# NANO_Mystical_Ouija_Board.net
KiCad netlist of a schematic drawn in EasyEDA
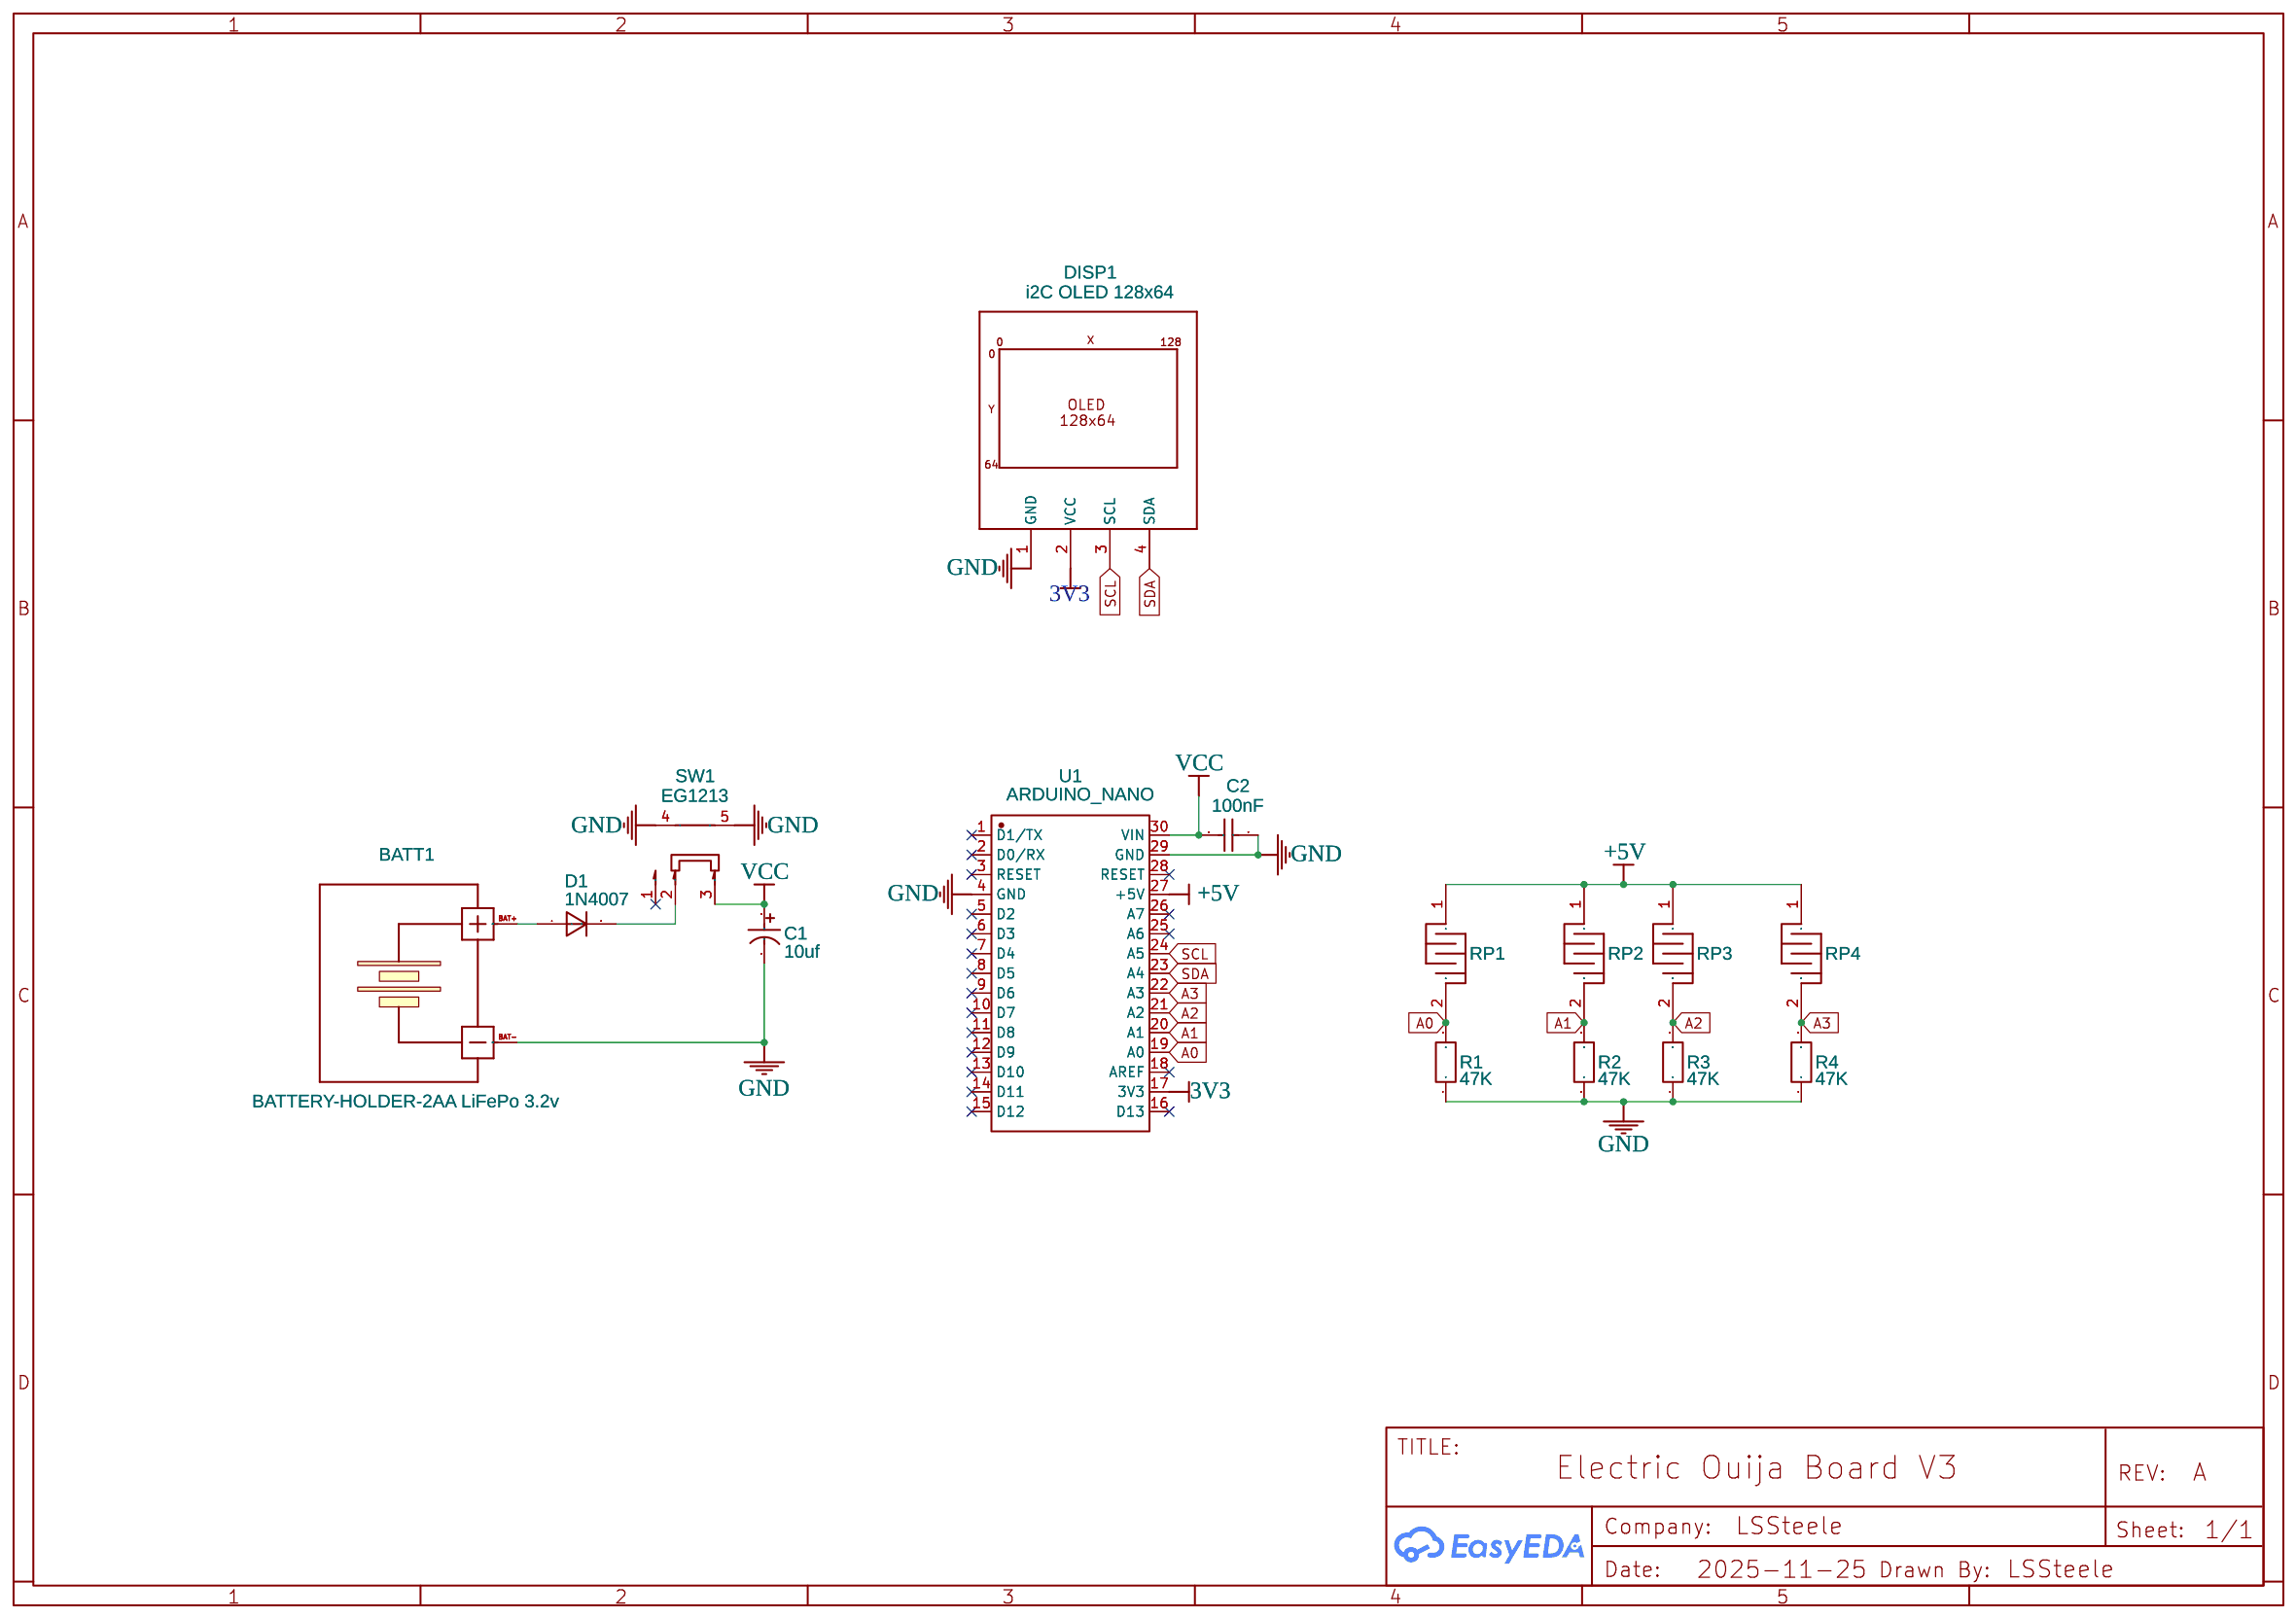
[diagram p0: schematic sheet]

(export (version "E")
  (design (tool "Eeschema 10.0.6"))
  (components
    (comp (ref "BATT1")
      (value "BATTERY-HOLDER-2AA LiFePo 3.2v")
      (libsource (lib "") (part "BATTERY-HOLDER-2AA"))
    )
    (comp (ref "C1") (value "10uf") (libsource (lib "") (part "Electrolytic Cap Small TH")))
    (comp (ref "C2")
      (value "100nF")
      (fields (field (name "Manufacturer Part") "CT4-0805Y104M500") (field (name "Manufacturer") "ReliaPro"))
      (libsource (lib "") (part "100nF"))
    )
    (comp (ref "D1") (value "1N4007") (libsource (lib "") (part "1N4007_Diode")))
    (comp (ref "DISP1") (value "i2C OLED 128x64") (libsource (lib "") (part "i2C OLED 128x64")))
    (comp (ref "R1")
      (value "47K")
      (fields (field (name "Manufacturer Part") "RD 1/4W 1R J T/B A1"))
      (libsource (lib "") (part "Resistor 1/4W TH"))
    )
    (comp (ref "R2")
      (value "47K")
      (fields (field (name "Manufacturer Part") "RD 1/4W 1R J T/B A1"))
      (libsource (lib "") (part "Resistor 1/4W TH"))
    )
    (comp (ref "R3")
      (value "47K")
      (fields (field (name "Manufacturer Part") "RD 1/4W 1R J T/B A1"))
      (libsource (lib "") (part "Resistor 1/4W TH"))
    )
    (comp (ref "R4")
      (value "47K")
      (fields (field (name "Manufacturer Part") "RD 1/4W 1R J T/B A1"))
      (libsource (lib "") (part "Resistor 1/4W TH"))
    )
    (comp (ref "RP1") (value "PCB_BUTTON 11MM") (libsource (lib "") (part "PCB_BUTTON 11MM")))
    (comp (ref "RP2") (value "PCB_BUTTON 11MM") (libsource (lib "") (part "PCB_BUTTON 11MM")))
    (comp (ref "RP3") (value "PCB_BUTTON 11MM") (libsource (lib "") (part "PCB_BUTTON 11MM")))
    (comp (ref "RP4") (value "PCB_BUTTON 11MM") (libsource (lib "") (part "PCB_BUTTON 11MM")))
    (comp (ref "SW1")
      (value "EG1213")
      (fields (field (name "Manufacturer") "E-Switch"))
      (libsource (lib "") (part "Power Switch_TH_EG1213"))
    )
    (comp (ref "U1") (value "ARDUINO_NANO") (libsource (lib "") (part "ARDUINO_NANO")))
  )
  (nets
    (net (code "1") (name "+5V") (class "Default")
      (node (ref "RP1") (pin "1") (pinfunction "1_1") (pintype "unspecified"))
      (node (ref "RP2") (pin "1") (pinfunction "1_1") (pintype "unspecified"))
      (node (ref "RP3") (pin "1") (pinfunction "1_1") (pintype "unspecified"))
      (node (ref "RP4") (pin "1") (pinfunction "1_1") (pintype "unspecified"))
      (node (ref "U1") (pin "27") (pinfunction "+5V_27") (pintype "unspecified"))
    )
    (net (code "2") (name "3V3") (class "Default")
      (node (ref "DISP1") (pin "2") (pinfunction "VCC_2") (pintype "bidirectional"))
      (node (ref "U1") (pin "17") (pinfunction "3V3_17") (pintype "unspecified"))
    )
    (net (code "3") (name "A0") (class "Default")
      (node (ref "R1") (pin "2") (pinfunction "2_2") (pintype "unspecified"))
      (node (ref "RP1") (pin "2") (pinfunction "2_2") (pintype "unspecified"))
      (node (ref "U1") (pin "19") (pinfunction "A0_19") (pintype "unspecified"))
    )
    (net (code "4") (name "A1") (class "Default")
      (node (ref "R2") (pin "2") (pinfunction "2_2") (pintype "unspecified"))
      (node (ref "RP2") (pin "2") (pinfunction "2_2") (pintype "unspecified"))
      (node (ref "U1") (pin "20") (pinfunction "A1_20") (pintype "unspecified"))
    )
    (net (code "5") (name "A2") (class "Default")
      (node (ref "R3") (pin "2") (pinfunction "2_2") (pintype "unspecified"))
      (node (ref "RP3") (pin "2") (pinfunction "2_2") (pintype "unspecified"))
      (node (ref "U1") (pin "21") (pinfunction "A2_21") (pintype "unspecified"))
    )
    (net (code "6") (name "A3") (class "Default")
      (node (ref "R4") (pin "2") (pinfunction "2_2") (pintype "unspecified"))
      (node (ref "RP4") (pin "2") (pinfunction "2_2") (pintype "unspecified"))
      (node (ref "U1") (pin "22") (pinfunction "A3_22") (pintype "unspecified"))
    )
    (net (code "7") (name "GND") (class "Default")
      (node (ref "BATT1") (pin "BAT-") (pinfunction "BAT-_BAT-") (pintype "bidirectional"))
      (node (ref "C1") (pin "2") (pinfunction "2_2") (pintype "input"))
      (node (ref "C2") (pin "2") (pinfunction "2_2") (pintype "input"))
      (node (ref "DISP1") (pin "1") (pinfunction "GND_1") (pintype "bidirectional"))
      (node (ref "R1") (pin "1") (pinfunction "1_1") (pintype "unspecified"))
      (node (ref "R2") (pin "1") (pinfunction "1_1") (pintype "unspecified"))
      (node (ref "R3") (pin "1") (pinfunction "1_1") (pintype "unspecified"))
      (node (ref "R4") (pin "1") (pinfunction "1_1") (pintype "unspecified"))
      (node (ref "SW1") (pin "4") (pinfunction "4_4") (pintype "unspecified"))
      (node (ref "SW1") (pin "5") (pinfunction "5_5") (pintype "unspecified"))
      (node (ref "U1") (pin "29") (pinfunction "GND_29") (pintype "unspecified"))
      (node (ref "U1") (pin "4") (pinfunction "GND_4") (pintype "unspecified"))
    )
    (net (code "8") (name "Net-(D1-A)") (class "Default")
      (node (ref "BATT1") (pin "BAT+") (pinfunction "BAT+_BAT+") (pintype "bidirectional"))
      (node (ref "D1") (pin "1") (pinfunction "A_1") (pintype "unspecified"))
    )
    (net (code "9") (name "Net-(D1-K)") (class "Default")
      (node (ref "D1") (pin "2") (pinfunction "K_2") (pintype "unspecified"))
      (node (ref "SW1") (pin "2") (pinfunction "2_2") (pintype "unspecified"))
    )
    (net (code "10") (name "SCL") (class "Default")
      (node (ref "DISP1") (pin "3") (pinfunction "SCL_3") (pintype "bidirectional"))
      (node (ref "U1") (pin "24") (pinfunction "A5_24") (pintype "unspecified"))
    )
    (net (code "11") (name "SDA") (class "Default")
      (node (ref "DISP1") (pin "4") (pinfunction "SDA_4") (pintype "bidirectional"))
      (node (ref "U1") (pin "23") (pinfunction "A4_23") (pintype "unspecified"))
    )
    (net (code "12") (name "VCC") (class "Default")
      (node (ref "C1") (pin "1") (pinfunction "1_1") (pintype "input"))
      (node (ref "C2") (pin "1") (pinfunction "1_1") (pintype "input"))
      (node (ref "SW1") (pin "3") (pinfunction "3_3") (pintype "unspecified"))
      (node (ref "U1") (pin "30") (pinfunction "VIN_30") (pintype "unspecified"))
    )
    (net (code "13") (name "unconnected-(SW1-Pad1)") (class "Default")
      (node (ref "SW1") (pin "1") (pinfunction "1_1") (pintype "unspecified+no_connect"))
    )
    (net (code "14") (name "unconnected-(U1-A6-Pad25)") (class "Default")
      (node (ref "U1") (pin "25") (pinfunction "A6_25") (pintype "unspecified+no_connect"))
    )
    (net (code "15") (name "unconnected-(U1-A7-Pad26)") (class "Default")
      (node (ref "U1") (pin "26") (pinfunction "A7_26") (pintype "unspecified+no_connect"))
    )
    (net (code "16") (name "unconnected-(U1-AREF-Pad18)") (class "Default")
      (node (ref "U1") (pin "18") (pinfunction "AREF_18") (pintype "unspecified+no_connect"))
    )
    (net (code "17") (name "unconnected-(U1-D0{slash}RX-Pad2)") (class "Default")
      (node (ref "U1") (pin "2") (pinfunction "D0/RX_2") (pintype "unspecified+no_connect"))
    )
    (net (code "18") (name "unconnected-(U1-D1{slash}TX-Pad1)") (class "Default")
      (node (ref "U1") (pin "1") (pinfunction "D1/TX_1") (pintype "unspecified+no_connect"))
    )
    (net (code "19") (name "unconnected-(U1-D2-Pad5)") (class "Default")
      (node (ref "U1") (pin "5") (pinfunction "D2_5") (pintype "unspecified+no_connect"))
    )
    (net (code "20") (name "unconnected-(U1-D3-Pad6)") (class "Default")
      (node (ref "U1") (pin "6") (pinfunction "D3_6") (pintype "unspecified+no_connect"))
    )
    (net (code "21") (name "unconnected-(U1-D4-Pad7)") (class "Default")
      (node (ref "U1") (pin "7") (pinfunction "D4_7") (pintype "unspecified+no_connect"))
    )
    (net (code "22") (name "unconnected-(U1-D5-Pad8)") (class "Default")
      (node (ref "U1") (pin "8") (pinfunction "D5_8") (pintype "unspecified+no_connect"))
    )
    (net (code "23") (name "unconnected-(U1-D6-Pad9)") (class "Default")
      (node (ref "U1") (pin "9") (pinfunction "D6_9") (pintype "unspecified+no_connect"))
    )
    (net (code "24") (name "unconnected-(U1-D7-Pad10)") (class "Default")
      (node (ref "U1") (pin "10") (pinfunction "D7_10") (pintype "unspecified+no_connect"))
    )
    (net (code "25") (name "unconnected-(U1-D8-Pad11)") (class "Default")
      (node (ref "U1") (pin "11") (pinfunction "D8_11") (pintype "unspecified+no_connect"))
    )
    (net (code "26") (name "unconnected-(U1-D9-Pad12)") (class "Default")
      (node (ref "U1") (pin "12") (pinfunction "D9_12") (pintype "unspecified+no_connect"))
    )
    (net (code "27") (name "unconnected-(U1-D10-Pad13)") (class "Default")
      (node (ref "U1") (pin "13") (pinfunction "D10_13") (pintype "unspecified+no_connect"))
    )
    (net (code "28") (name "unconnected-(U1-D11-Pad14)") (class "Default")
      (node (ref "U1") (pin "14") (pinfunction "D11_14") (pintype "unspecified+no_connect"))
    )
    (net (code "29") (name "unconnected-(U1-D12-Pad15)") (class "Default")
      (node (ref "U1") (pin "15") (pinfunction "D12_15") (pintype "unspecified+no_connect"))
    )
    (net (code "30") (name "unconnected-(U1-D13-Pad16)") (class "Default")
      (node (ref "U1") (pin "16") (pinfunction "D13_16") (pintype "unspecified+no_connect"))
    )
    (net (code "31") (name "unconnected-(U1-RESET-Pad3)") (class "Default")
      (node (ref "U1") (pin "3") (pinfunction "RESET_3") (pintype "unspecified+no_connect"))
    )
    (net (code "32") (name "unconnected-(U1-RESET-Pad28)") (class "Default")
      (node (ref "U1") (pin "28") (pinfunction "RESET_28") (pintype "unspecified+no_connect"))
    )
  )
)
